# Indicators.net
KiCad netlist of a schematic drawn in Altium Designer
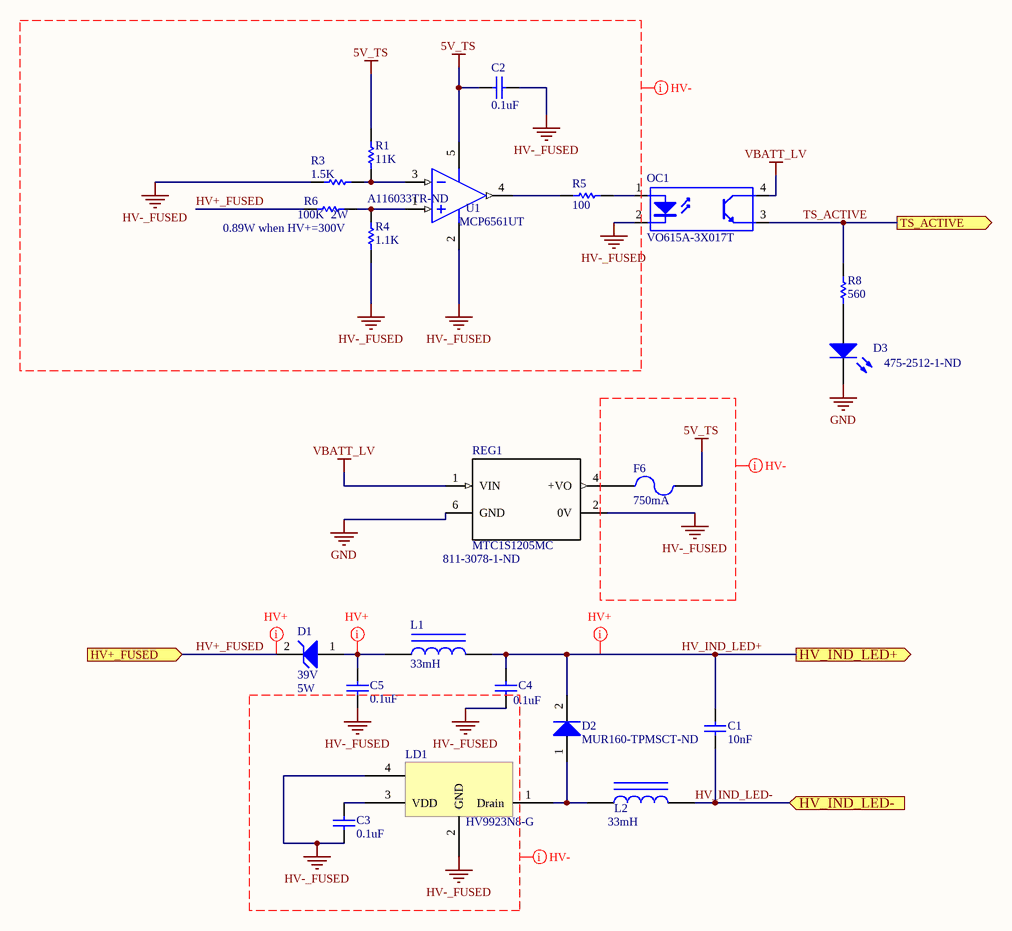
[diagram p0: Indicators.SchDoc]

(export (version "E")
  (design (tool "Eeschema 10.0.6"))
  (components
    (comp (ref "C1")
      (value "10nF")
      (footprint "0805R-GENERIC")
      (description "885342207014:  CAP CER 10000PF 500V X7R 0805")
      (fields (field (name "PUBLISHER") "Altium Limited"))
      (libsource (lib "Miscellaneous Devices") (part "Cap"))
    )
    (comp (ref "C2")
      (value "0.1uF")
      (footprint "1206R-GENERIC")
      (description "CGA5L4X7T2W104M160AA: CAP CER 0.1UF 450V X7T 1206")
      (fields (field (name "PUBLISHER") "Altium Limited"))
      (libsource (lib "Miscellaneous Devices") (part "Cap"))
    )
    (comp (ref "C3")
      (value "0.1uF")
      (footprint "1206R-GENERIC")
      (description "CGA5L4X7T2W104M160AA: CAP CER 0.1UF 450V X7T 1206")
      (fields (field (name "PUBLISHER") "Altium Limited"))
      (libsource (lib "Miscellaneous Devices") (part "Cap"))
    )
    (comp (ref "C4")
      (value "0.1uF")
      (footprint "1206R-GENERIC")
      (description "CGA5L4X7T2W104M160AA: CAP CER 0.1UF 450V X7T 1206")
      (fields (field (name "PUBLISHER") "Altium Limited"))
      (libsource (lib "Miscellaneous Devices") (part "Cap"))
    )
    (comp (ref "C5")
      (value "0.1uF")
      (footprint "1206R-GENERIC")
      (description "CGA5L4X7T2W104M160AA: CAP CER 0.1UF 450V X7T 1206")
      (fields (field (name "PUBLISHER") "Altium Limited"))
      (libsource (lib "Miscellaneous Devices") (part "Cap"))
    )
    (comp (ref "D1")
      (value "SMBJ5366B-TP")
      (footprint "DO-214AA")
      (description "DIODE ZENER 39V 5W DO214AA")
      (fields
        (field (name "VOLTAGE") "39V")
        (field (name "POWER") "5W")
        (field (name "PUBLISHER") "Altium Limited")
      )
      (libsource (lib "Miscellaneous Devices") (part "D Zener"))
    )
    (comp (ref "D2")
      (value "MUR160-TPMSCT-ND")
      (footprint "DO-41")
      (description "DIODE GEN PURP 600V 1A DO41")
      (fields (field (name "PUBLISHER") "Altium Limited"))
      (libsource (lib "Miscellaneous Devices") (part "Diode 1N914"))
    )
    (comp (ref "D3")
      (value "~")
      (footprint "J1-0603")
      (description "Typical RED, GREEN, YELLOW, AMBER GaAs LED")
      (fields (field (name "SUPPLIERPARTNO") "475-2512-1-ND") (field (name "PUBLISHER") "Altium Limited"))
      (libsource (lib "Miscellaneous Devices") (part "LED2"))
    )
    (comp (ref "F6")
      (value "750mA")
      (footprint "FUSEHOLDER 5X20")
      (description "0031.8201: FUSE BLOK CARTRIDGE 500V 10A PCB")
      (fields (field (name "PUBLISHER") "Altium Limited"))
      (libsource (lib "Miscellaneous Devices") (part "Fuse 2"))
    )
    (comp (ref "L1")
      (value "33mH")
      (footprint "Radial - 3mm")
      (description "22R336C: FIXED IND 33MH 36MA 118.8 OHM TH")
      (fields (field (name "PUBLISHER") "Altium Limited"))
      (libsource (lib "Miscellaneous Devices") (part "Inductor Iron"))
    )
    (comp (ref "L2")
      (value "33mH")
      (footprint "Radial - 3mm")
      (description "22R336C: FIXED IND 33MH 36MA 118.8 OHM TH")
      (fields (field (name "PUBLISHER") "Altium Limited"))
      (libsource (lib "Miscellaneous Devices") (part "Inductor Iron"))
    )
    (comp (ref "LD1")
      (value "HV9923N8-G")
      (footprint "TO-243AA")
      (description "IC LED Driver AC DC Offline Switcher Triac Dimming 30mA Lighting SOT-89-3")
      (libsource (lib "FE Schem Lib") (part "1-776163-5"))
    )
    (comp (ref "OC1")
      (value "VO615A-3X017T")
      (footprint "Optocoupler")
      (description "OPTOISOLATR 5KV TRANSISTOR 4-SMD")
      (fields (field (name "PUBLISHER") "Altium Limited"))
      (libsource (lib "Miscellaneous Devices") (part "Optoisolator1"))
    )
    (comp (ref "R1")
      (value "11K")
      (footprint "1206R-GENERIC")
      (description "KTR18EZPF1102: RES SMD 11K OHM 1% 1/4W 1206")
      (fields (field (name "PUBLISHER") "Altium Limited"))
      (libsource (lib "Miscellaneous Devices") (part "Res1"))
    )
    (comp (ref "R3")
      (value "1.5K")
      (footprint "1206R-GENERIC")
      (description "KTR18EZPF1501: RES SMD 1.5K OHM 1% 1/4W 1206")
      (fields (field (name "PUBLISHER") "Altium Limited"))
      (libsource (lib "Miscellaneous Devices") (part "Res1"))
    )
    (comp (ref "R4")
      (value "1.1K")
      (footprint "1206R-GENERIC")
      (description "RT1210BRD071K1L: RES SMD 1.1K OHM 0.1% 1/4W 1210")
      (fields
        (field (name "SUPPLIER PART NUMBER 2") "A116033TR-ND")
        (field (name "PUBLISHER") "Altium Limited")
      )
      (libsource (lib "Miscellaneous Devices") (part "Res1"))
    )
    (comp (ref "R5")
      (value "100")
      (footprint "1206R-GENERIC")
      (description "KTR18EZPJ101: RES SMD 100 OHM 5% 1/4W 1206")
      (fields (field (name "PUBLISHER") "Altium Limited"))
      (libsource (lib "Miscellaneous Devices") (part "Res1"))
    )
    (comp (ref "R6")
      (value "100K")
      (footprint "RESC2512(6432)_N")
      (description "HVCB2512FKC100K: RES SMD 100K OHM 1% 2W 2512")
      (fields (field (name "POWER") "2W") (field (name "TOLERANCE") "5 %"))
      (libsource (lib "Altium Content Vault") (part "CMP-1018-00122-1"))
    )
    (comp (ref "R8")
      (value "560")
      (footprint "J1-0603")
      (description "KTR18EZPJ101: RES SMD 100 OHM 5% 1/4W 1206")
      (fields (field (name "PUBLISHER") "Altium Limited"))
      (libsource (lib "Miscellaneous Devices") (part "Res1"))
    )
    (comp (ref "REG1")
      (value "MTC1S1205MC")
      (footprint "MTC1S1205MC")
      (fields (field (name "SUPPLIERPARTNO") "811-3078-1-ND"))
      (libsource (lib "MTC1S1205MC") (part "MTC1S1205MC"))
    )
    (comp (ref "U1")
      (value "MCP6561UT")
      (footprint "SOT-23-OT5_N")
      (libsource (lib "Altium Content Vault") (part "CMP-0187-00428-2"))
    )
  )
  (nets
    (net (code "1") (name "/HV+_FUSED") (class "Default")
      (node (ref "D1") (pin "2") (pinfunction "K_2") (pintype "passive"))
      (node (ref "R6") (pin "2") (pinfunction "2_2") (pintype "passive"))
    )
    (net (code "2") (name "/HV_IND_LED+") (class "Default")
      (node (ref "C1") (pin "2") (pinfunction "2_2") (pintype "passive"))
      (node (ref "C4") (pin "2") (pinfunction "2_2") (pintype "passive"))
      (node (ref "D2") (pin "2") (pinfunction "K_2") (pintype "passive"))
      (node (ref "L1") (pin "2") (pinfunction "2_2") (pintype "passive"))
    )
    (net (code "3") (name "/HV_IND_LED-") (class "Default")
      (node (ref "C1") (pin "1") (pinfunction "1_1") (pintype "passive"))
      (node (ref "L2") (pin "2") (pinfunction "2_2") (pintype "passive"))
    )
    (net (code "4") (name "/TS_ACTIVE") (class "Default")
      (node (ref "OC1") (pin "3") (pinfunction "E_3") (pintype "passive"))
      (node (ref "R8") (pin "2") (pinfunction "2_2") (pintype "passive"))
    )
    (net (code "5") (name "5V_TS") (class "Default")
      (node (ref "C2") (pin "2") (pinfunction "2_2") (pintype "passive"))
      (node (ref "F6") (pin "1") (pinfunction "1_1") (pintype "passive"))
      (node (ref "R1") (pin "1") (pinfunction "1_1") (pintype "passive"))
      (node (ref "U1") (pin "5") (pinfunction "VDD_5") (pintype "power_in"))
    )
    (net (code "6") (name "GND") (class "Default")
      (node (ref "D3") (pin "2") (pinfunction "K_2") (pintype "passive"))
      (node (ref "REG1") (pin "6") (pinfunction "GND_6") (pintype "power_in"))
    )
    (net (code "7") (name "HV-_FUSED") (class "Default")
      (node (ref "C2") (pin "1") (pinfunction "1_1") (pintype "passive"))
      (node (ref "C3") (pin "1") (pinfunction "1_1") (pintype "passive"))
      (node (ref "C4") (pin "1") (pinfunction "1_1") (pintype "passive"))
      (node (ref "C5") (pin "2") (pinfunction "2_2") (pintype "passive"))
      (node (ref "LD1") (pin "2") (pinfunction "GND_2") (pintype "passive"))
      (node (ref "LD1") (pin "4") (pintype "passive"))
      (node (ref "OC1") (pin "2") (pinfunction "K_2") (pintype "passive"))
      (node (ref "R3") (pin "1") (pinfunction "1_1") (pintype "passive"))
      (node (ref "R4") (pin "2") (pinfunction "2_2") (pintype "passive"))
      (node (ref "REG1") (pin "2") (pinfunction "0V_2") (pintype "power_in"))
      (node (ref "U1") (pin "2") (pinfunction "VSS_2") (pintype "power_in"))
    )
    (net (code "8") (name "Net-(D1-A)") (class "Default")
      (node (ref "C5") (pin "1") (pinfunction "1_1") (pintype "passive"))
      (node (ref "D1") (pin "1") (pinfunction "A_1") (pintype "passive"))
      (node (ref "L1") (pin "1") (pinfunction "1_1") (pintype "passive"))
    )
    (net (code "9") (name "Net-(D2-A)") (class "Default")
      (node (ref "D2") (pin "1") (pinfunction "A_1") (pintype "passive"))
      (node (ref "L2") (pin "1") (pinfunction "1_1") (pintype "passive"))
      (node (ref "LD1") (pin "1") (pinfunction "Drain_1") (pintype "passive"))
    )
    (net (code "10") (name "Net-(D3-A)") (class "Default")
      (node (ref "D3") (pin "1") (pinfunction "A_1") (pintype "passive"))
      (node (ref "R8") (pin "1") (pinfunction "1_1") (pintype "passive"))
    )
    (net (code "11") (name "Net-(LD1-VDD)") (class "Default")
      (node (ref "C3") (pin "2") (pinfunction "2_2") (pintype "passive"))
      (node (ref "LD1") (pin "3") (pinfunction "VDD_3") (pintype "passive"))
    )
    (net (code "12") (name "Net-(OC1-A)") (class "Default")
      (node (ref "OC1") (pin "1") (pinfunction "A_1") (pintype "passive"))
      (node (ref "R5") (pin "2") (pinfunction "2_2") (pintype "passive"))
    )
    (net (code "13") (name "Net-(REG1-+VO)") (class "Default")
      (node (ref "F6") (pin "2") (pinfunction "2_2") (pintype "passive"))
      (node (ref "REG1") (pin "4") (pinfunction "+VO_4") (pintype "output"))
    )
    (net (code "14") (name "Net-(U1-OUT)") (class "Default")
      (node (ref "R5") (pin "1") (pinfunction "1_1") (pintype "passive"))
      (node (ref "U1") (pin "4") (pinfunction "OUT_4") (pintype "output"))
    )
    (net (code "15") (name "Net-(U1-VIN+)") (class "Default")
      (node (ref "R4") (pin "1") (pinfunction "1_1") (pintype "passive"))
      (node (ref "R6") (pin "1") (pinfunction "1_1") (pintype "passive"))
      (node (ref "U1") (pin "1") (pinfunction "VIN+_1") (pintype "input"))
    )
    (net (code "16") (name "Net-(U1-VIN-)") (class "Default")
      (node (ref "R1") (pin "2") (pinfunction "2_2") (pintype "passive"))
      (node (ref "R3") (pin "2") (pinfunction "2_2") (pintype "passive"))
      (node (ref "U1") (pin "3") (pinfunction "VIN-_3") (pintype "input"))
    )
    (net (code "17") (name "VBATT_LV") (class "Default")
      (node (ref "OC1") (pin "4") (pinfunction "C_4") (pintype "passive"))
      (node (ref "REG1") (pin "1") (pinfunction "VIN_1") (pintype "input"))
    )
  )
)
